# HB_PowerSupply.net
KiCad netlist of a schematic drawn in Altium Designer
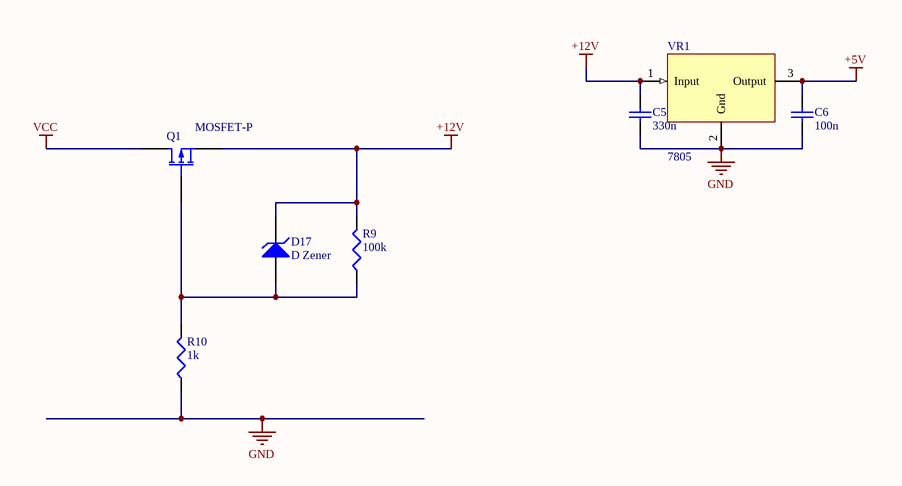
[diagram p0: HB_PowerSupply.SchDoc]

(export (version "E")
  (design (tool "Eeschema 10.0.6"))
  (components
    (comp (ref "C5")
      (value "330n")
      (footprint "C1206")
      (description "Condensateur")
      (fields (field (name "Comment") "Cap_330n") (field (name "DESIGNER") "ECAM 2004"))
      (libsource (lib "HBLib") (part "Cap_330n"))
    )
    (comp (ref "C6")
      (value "100n")
      (footprint "C1206")
      (description "Condensateur")
      (fields (field (name "Comment") "Cap_100n") (field (name "DESIGNER") "ECAM 2004"))
      (libsource (lib "HBLib") (part "Cap_100n"))
    )
    (comp (ref "D17")
      (value "D Zener")
      (footprint "SOD-123")
      (description "Zener Diode")
      (fields (field (name "PUBLISHER") "Altium Limited"))
      (libsource (lib "HBLib") (part "D Zener"))
    )
    (comp (ref "Q1")
      (value "MOSFET-P")
      (footprint "TO-220-AB")
      (description "P-Channel MOSFET")
      (fields (field (name "PUBLISHER") "Altium Limited"))
      (libsource (lib "HBLib") (part "MOSFET-P"))
    )
    (comp (ref "R9")
      (value "100k")
      (footprint "6-0805_L")
      (description "Résistance standard")
      (fields (field (name "Comment") "Res_100k") (field (name "DESIGNER") "ECAM 2005"))
      (libsource (lib "HBLib") (part "Res_100k"))
    )
    (comp (ref "R10")
      (value "1k")
      (footprint "6-0805_L")
      (description "Résistance standard")
      (fields (field (name "Comment") "Res_1k") (field (name "DESIGNER") "ECAM 2005"))
      (libsource (lib "HBLib") (part "Res_1k"))
    )
    (comp (ref "VR1")
      (value "7805")
      (footprint "TO-220AB")
      (description "Régulateur 5V")
      (fields (field (name "TYPE") "7805") (field (name "DESIGNER") "ECAM 2004"))
      (libsource (lib "HBLib") (part "7805"))
    )
  )
  (nets
    (net (code "1") (name "+5V") (class "Default")
      (node (ref "C6") (pin "1") (pinfunction "1_1") (pintype "passive"))
      (node (ref "VR1") (pin "3") (pinfunction "Output_3") (pintype "power_in"))
    )
    (net (code "2") (name "+12V") (class "Default")
      (node (ref "C5") (pin "1") (pinfunction "1_1") (pintype "passive"))
      (node (ref "D17") (pin "1") (pinfunction "K_1") (pintype "passive"))
      (node (ref "Q1") (pin "S") (pinfunction "S_S") (pintype "passive"))
      (node (ref "R9") (pin "2") (pinfunction "2_2") (pintype "passive"))
      (node (ref "VR1") (pin "1") (pinfunction "Input_1") (pintype "input"))
    )
    (net (code "3") (name "GND") (class "Default")
      (node (ref "C5") (pin "2") (pinfunction "2_2") (pintype "passive"))
      (node (ref "C6") (pin "2") (pinfunction "2_2") (pintype "passive"))
      (node (ref "R10") (pin "1") (pinfunction "1_1") (pintype "passive"))
      (node (ref "VR1") (pin "2") (pinfunction "Gnd_2") (pintype "power_in"))
    )
    (net (code "4") (name "Net-(D17-A)") (class "Default")
      (node (ref "D17") (pin "2") (pinfunction "A_2") (pintype "passive"))
      (node (ref "Q1") (pin "G") (pinfunction "G_G") (pintype "passive"))
      (node (ref "R10") (pin "2") (pinfunction "2_2") (pintype "passive"))
      (node (ref "R9") (pin "1") (pinfunction "1_1") (pintype "passive"))
    )
    (net (code "5") (name "VCC") (class "Default")
      (node (ref "Q1") (pin "D") (pinfunction "D_D") (pintype "passive"))
    )
  )
)
